# USB-RS232_A2.net
KiCad netlist of a schematic drawn in Altium Designer
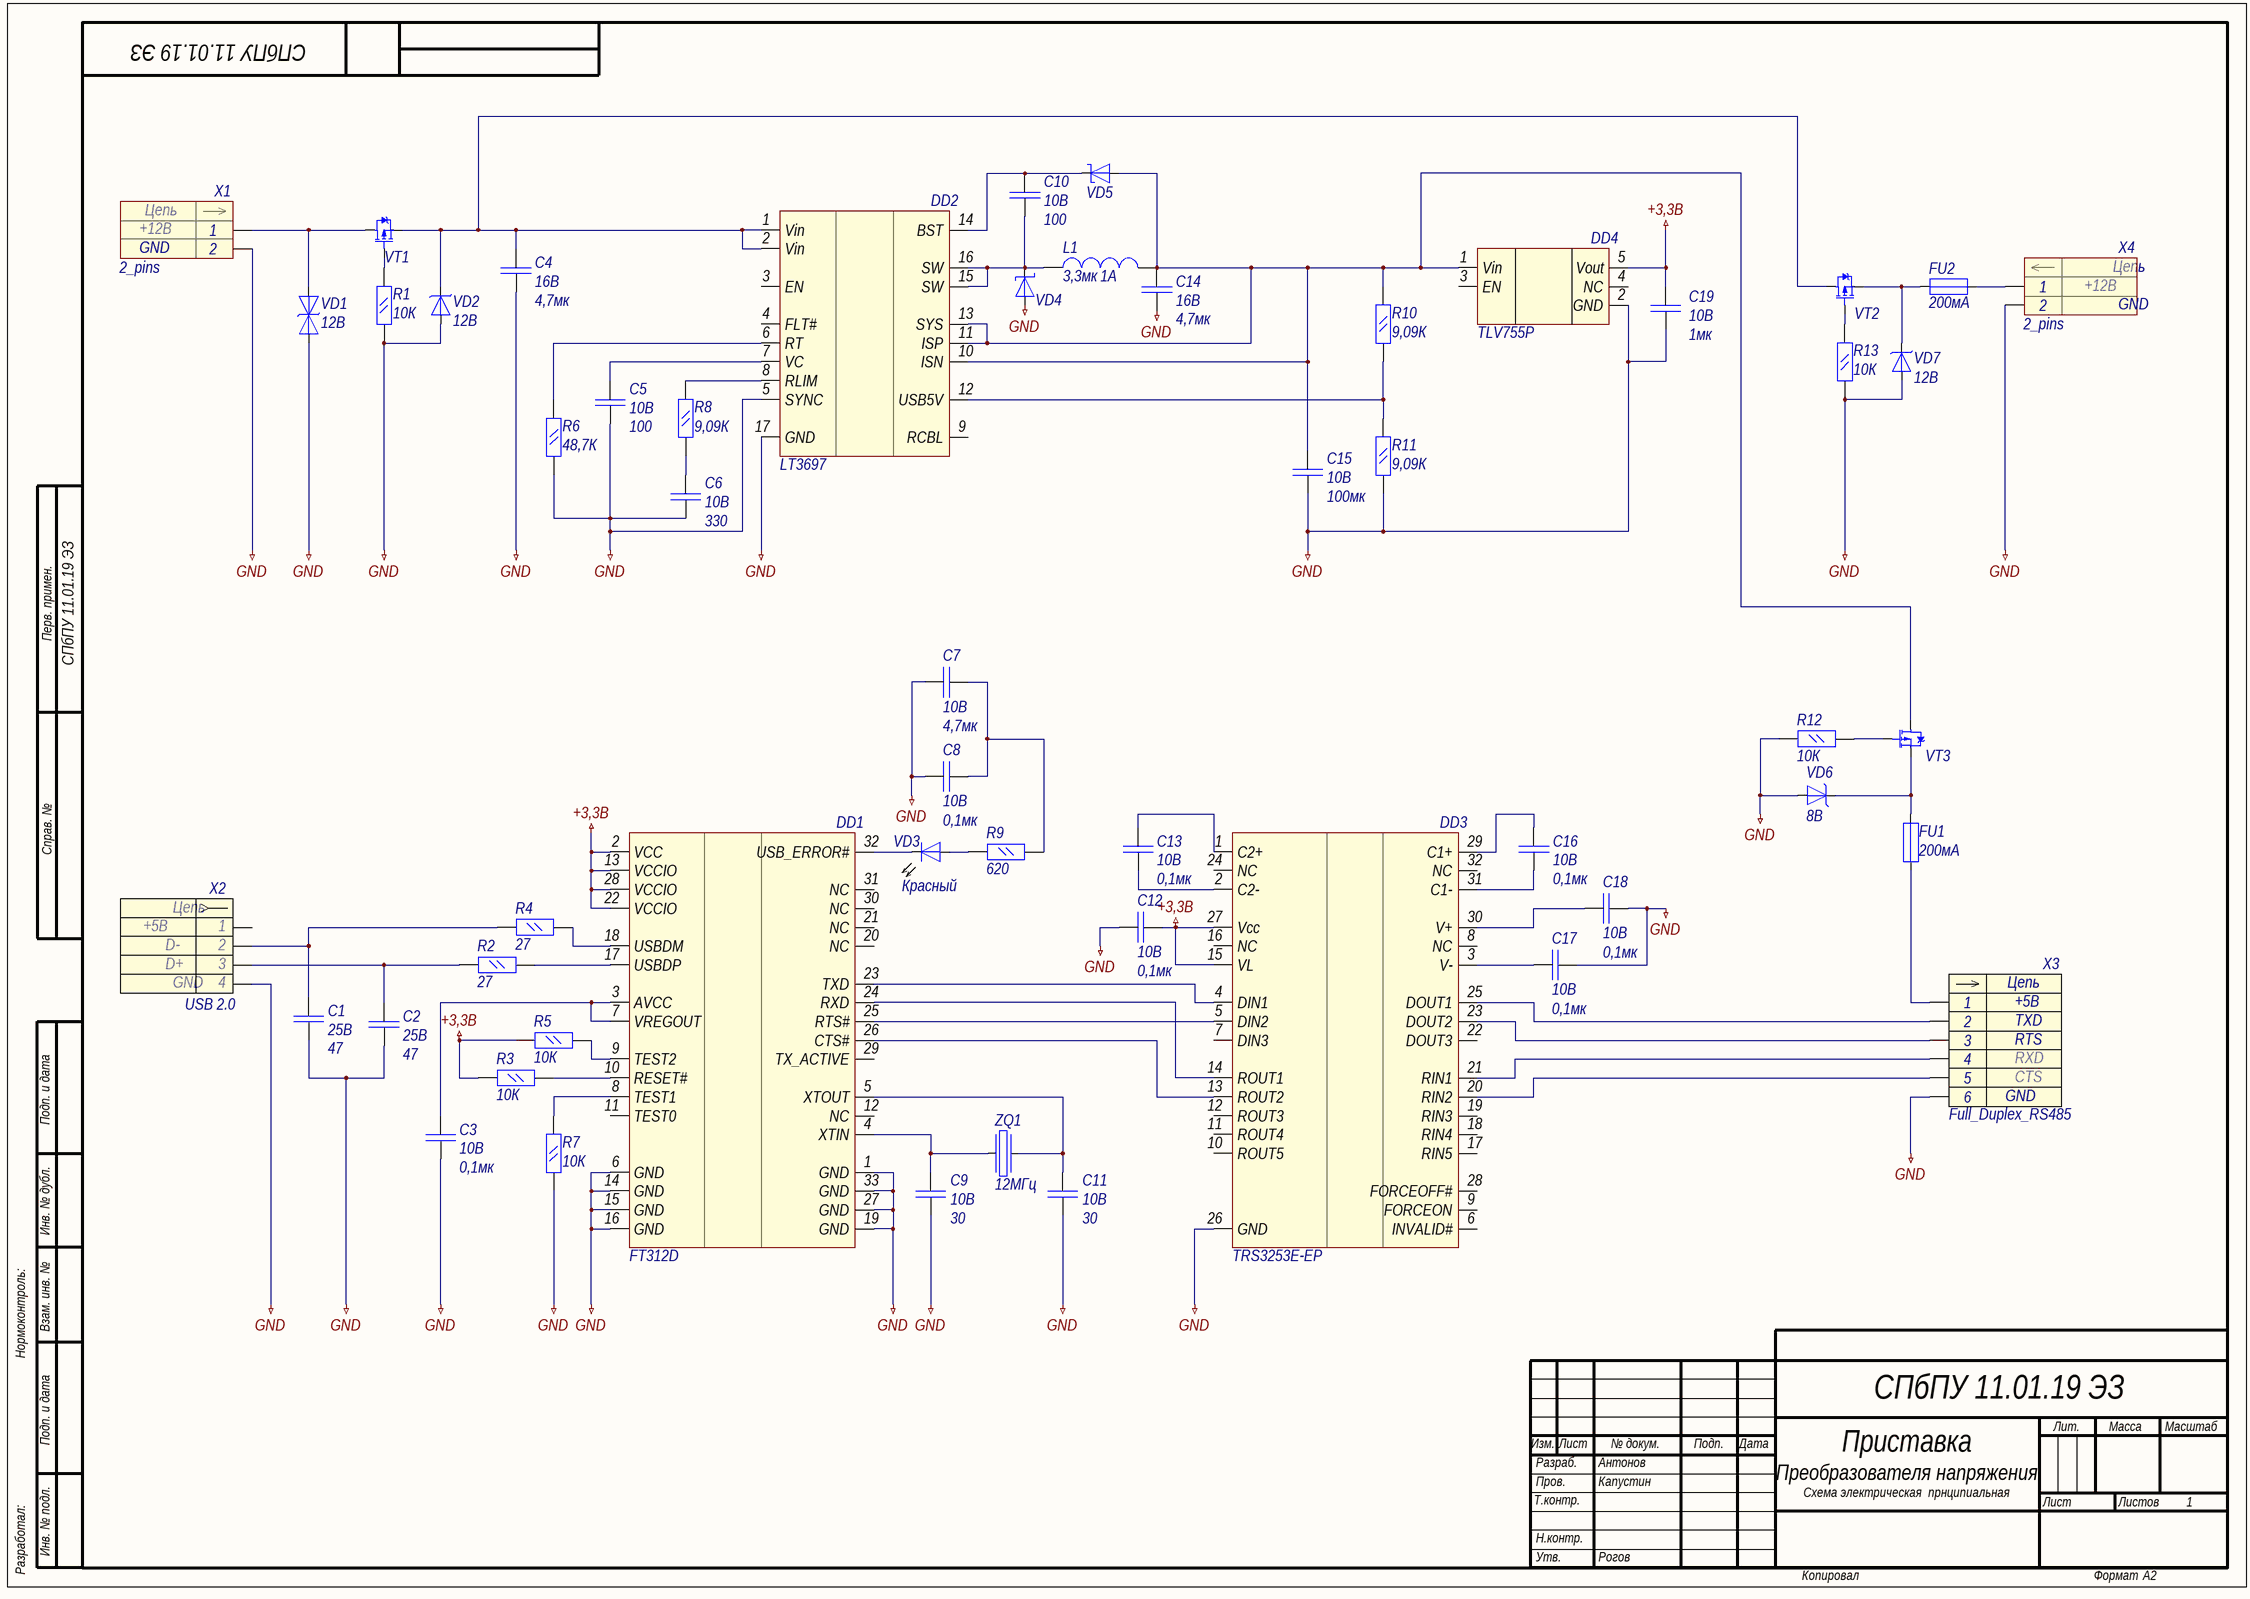
[diagram p0: USB-RS232_A2.SchDoc]

(export (version "E")
  (design (tool "Eeschema 10.0.6"))
  (components
    (comp (ref "C1")
      (value "Capacitor")
      (footprint "CH0201C")
      (fields (field (name "VOLTAGE") "25В") (field (name "CAPACITANCE") "47"))
      (libsource (lib "GOST_Capacitors") (part "Capacitor"))
    )
    (comp (ref "C2")
      (value "Capacitor")
      (footprint "CH0201C")
      (fields (field (name "VOLTAGE") "25В") (field (name "CAPACITANCE") "47"))
      (libsource (lib "GOST_Capacitors") (part "Capacitor"))
    )
    (comp (ref "C3")
      (value "Capacitor")
      (footprint "CH0402C")
      (fields (field (name "VOLTAGE") "10В") (field (name "CAPACITANCE") "0,1мк"))
      (libsource (lib "GOST_Capacitors") (part "Capacitor"))
    )
    (comp (ref "C4")
      (value "Capacitor")
      (footprint "CH0603C")
      (fields (field (name "VOLTAGE") "16В") (field (name "CAPACITANCE") "4,7мк"))
      (libsource (lib "GOST_Capacitors") (part "Capacitor"))
    )
    (comp (ref "C5")
      (value "Capacitor")
      (footprint "CH0201C")
      (fields (field (name "VOLTAGE") "10В") (field (name "CAPACITANCE") "100"))
      (libsource (lib "GOST_Capacitors") (part "Capacitor"))
    )
    (comp (ref "C6")
      (value "Capacitor")
      (footprint "CH0402C")
      (fields (field (name "VOLTAGE") "10В") (field (name "CAPACITANCE") "330"))
      (libsource (lib "GOST_Capacitors") (part "Capacitor"))
    )
    (comp (ref "C7")
      (value "Capacitor")
      (footprint "CH0402C")
      (fields (field (name "VOLTAGE") "10В") (field (name "CAPACITANCE") "4,7мк"))
      (libsource (lib "GOST_Capacitors") (part "Capacitor"))
    )
    (comp (ref "C8")
      (value "Capacitor")
      (footprint "CH0402C")
      (fields (field (name "VOLTAGE") "10В") (field (name "CAPACITANCE") "0,1мк"))
      (libsource (lib "GOST_Capacitors") (part "Capacitor"))
    )
    (comp (ref "C9")
      (value "Capacitor")
      (footprint "CH0201C")
      (fields (field (name "VOLTAGE") "10В") (field (name "CAPACITANCE") "30"))
      (libsource (lib "GOST_Capacitors") (part "Capacitor"))
    )
    (comp (ref "C10")
      (value "Capacitor")
      (footprint "CH0201C")
      (fields (field (name "VOLTAGE") "10В") (field (name "CAPACITANCE") "100"))
      (libsource (lib "GOST_Capacitors") (part "Capacitor"))
    )
    (comp (ref "C11")
      (value "Capacitor")
      (footprint "CH0201C")
      (fields (field (name "VOLTAGE") "10В") (field (name "CAPACITANCE") "30"))
      (libsource (lib "GOST_Capacitors") (part "Capacitor"))
    )
    (comp (ref "C12")
      (value "Capacitor")
      (footprint "CH0402C")
      (fields (field (name "VOLTAGE") "10В") (field (name "CAPACITANCE") "0,1мк"))
      (libsource (lib "GOST_Capacitors") (part "Capacitor"))
    )
    (comp (ref "C13")
      (value "Capacitor")
      (footprint "CH0402C")
      (fields (field (name "VOLTAGE") "10В") (field (name "CAPACITANCE") "0,1мк"))
      (libsource (lib "GOST_Capacitors") (part "Capacitor"))
    )
    (comp (ref "C14")
      (value "Capacitor")
      (footprint "CH0603C")
      (fields (field (name "VOLTAGE") "16В") (field (name "CAPACITANCE") "4,7мк"))
      (libsource (lib "GOST_Capacitors") (part "Capacitor"))
    )
    (comp (ref "C15")
      (value "Capacitor")
      (footprint "CH1206C")
      (fields (field (name "VOLTAGE") "10В") (field (name "CAPACITANCE") "100мк"))
      (libsource (lib "GOST_Capacitors") (part "Capacitor"))
    )
    (comp (ref "C16")
      (value "Capacitor")
      (footprint "CH0402C")
      (fields (field (name "VOLTAGE") "10В") (field (name "CAPACITANCE") "0,1мк"))
      (libsource (lib "GOST_Capacitors") (part "Capacitor"))
    )
    (comp (ref "C17")
      (value "Capacitor")
      (footprint "CH0402C")
      (fields (field (name "VOLTAGE") "10В") (field (name "CAPACITANCE") "0,1мк"))
      (libsource (lib "GOST_Capacitors") (part "Capacitor"))
    )
    (comp (ref "C18")
      (value "Capacitor")
      (footprint "CH0402C")
      (fields (field (name "VOLTAGE") "10В") (field (name "CAPACITANCE") "0,1мк"))
      (libsource (lib "GOST_Capacitors") (part "Capacitor"))
    )
    (comp (ref "C19")
      (value "Capacitor")
      (footprint "CH0201C")
      (fields (field (name "VOLTAGE") "10В") (field (name "CAPACITANCE") "1мк"))
      (libsource (lib "GOST_Capacitors") (part "Capacitor"))
    )
    (comp (ref "DD1")
      (value "FT312D")
      (footprint "FT312D")
      (description "Ivan")
      (libsource (lib "GOST_lib_devices") (part "FT312D"))
    )
    (comp (ref "DD2")
      (value "LT3697")
      (footprint "LT3697")
      (description "6~18 to 5")
      (libsource (lib "GOST_lib_devices") (part "LT3697"))
    )
    (comp (ref "DD3")
      (value "TRS3253E-EP")
      (footprint "TRS3253E-EP")
      (description "UART - RS232")
      (libsource (lib "GOST_lib_devices") (part "TRS3253E-EP"))
    )
    (comp (ref "DD4")
      (value "TLV755P")
      (footprint "SOT23-5")
      (libsource (lib "GOST_lib_devices") (part "LDO +3.3V"))
    )
    (comp (ref "FU1")
      (value "200мА")
      (footprint "CH0402R")
      (fields (field (name "Comment") "Fuse"))
      (libsource (lib "GOST_Miscelanuious") (part "Fuse"))
    )
    (comp (ref "FU2")
      (value "200мА")
      (footprint "CH0402R")
      (fields (field (name "Comment") "Fuse"))
      (libsource (lib "") (part "Fuse_1"))
    )
    (comp (ref "L1")
      (value "*")
      (footprint "CH0805L")
      (fields (field (name "MAX CURRENT") "1А") (field (name "INDUCTANCE") "3,3мк"))
      (libsource (lib "GOST_Inductors") (part "Inductor"))
    )
    (comp (ref "R1")
      (value "Res_0.125")
      (footprint "CH0402R")
      (fields (field (name "IMPEDANCE") "10К"))
      (libsource (lib "GOST_Resistors") (part "Res_0.125"))
    )
    (comp (ref "R2")
      (value "Res_0.125")
      (footprint "CH0402R")
      (fields (field (name "IMPEDANCE") "27"))
      (libsource (lib "GOST_Resistors") (part "Res_0.125"))
    )
    (comp (ref "R3")
      (value "Res_0.125")
      (footprint "CH0402R")
      (fields (field (name "IMPEDANCE") "10К"))
      (libsource (lib "GOST_Resistors") (part "Res_0.125"))
    )
    (comp (ref "R4")
      (value "Res_0.125")
      (footprint "CH0402R")
      (fields (field (name "IMPEDANCE") "27"))
      (libsource (lib "GOST_Resistors") (part "Res_0.125"))
    )
    (comp (ref "R5")
      (value "Res_0.125")
      (footprint "CH0402R")
      (fields (field (name "IMPEDANCE") "10К"))
      (libsource (lib "GOST_Resistors") (part "Res_0.125"))
    )
    (comp (ref "R6")
      (value "Res_0.125")
      (footprint "CH0805R")
      (fields (field (name "IMPEDANCE") "48,7К"))
      (libsource (lib "GOST_Resistors") (part "Res_0.125"))
    )
    (comp (ref "R7")
      (value "Res_0.125")
      (footprint "CH0402R")
      (fields (field (name "IMPEDANCE") "10К"))
      (libsource (lib "GOST_Resistors") (part "Res_0.125"))
    )
    (comp (ref "R8")
      (value "Res_0.125")
      (footprint "CH0805R")
      (fields (field (name "IMPEDANCE") "9,09К"))
      (libsource (lib "GOST_Resistors") (part "Res_0.125"))
    )
    (comp (ref "R9")
      (value "Res_0.125")
      (footprint "CH0402R")
      (fields (field (name "IMPEDANCE") "620"))
      (libsource (lib "GOST_Resistors") (part "Res_0.125"))
    )
    (comp (ref "R10")
      (value "Res_0.125")
      (footprint "CH0805R")
      (fields (field (name "IMPEDANCE") "9,09К"))
      (libsource (lib "GOST_Resistors") (part "Res_0.125"))
    )
    (comp (ref "R11")
      (value "Res_0.125")
      (footprint "CH0805R")
      (fields (field (name "IMPEDANCE") "9,09К"))
      (libsource (lib "GOST_Resistors") (part "Res_0.125"))
    )
    (comp (ref "R12")
      (value "Res_0.125")
      (footprint "CH0402R")
      (fields (field (name "IMPEDANCE") "10К"))
      (libsource (lib "GOST_Resistors") (part "Res_0.125"))
    )
    (comp (ref "R13")
      (value "Res_0.125")
      (footprint "CH0402R")
      (fields (field (name "IMPEDANCE") "10К"))
      (libsource (lib "GOST_Resistors") (part "Res_0.125"))
    )
    (comp (ref "VD1")
      (value "TVS-diod_simmetrical")
      (footprint "CH0201L")
      (fields (field (name "MANUFACTURER") "Littelfuse") (field (name "CLAMPING VOLTAGE") "12В"))
      (libsource (lib "GOST_Diodes") (part "TVS-diod_simmetrical"))
    )
    (comp (ref "VD2")
      (value "TVS-diod_directed")
      (footprint "DO214AA")
      (fields (field (name "MANUFACTURER") "Bourns") (field (name "CLAMPING_VOLTAGE") "12В"))
      (libsource (lib "GOST_Diodes") (part "TVS-diod_directed"))
    )
    (comp (ref "VD3")
      (value "Light_diod")
      (footprint "CH0201L")
      (fields (field (name "COLOR") "Красный"))
      (libsource (lib "GOST_Diodes") (part "Light_diod"))
    )
    (comp (ref "VD4")
      (value "Diod Schottky")
      (footprint "DO214AA")
      (fields (field (name "MANUFACTURER") "Rectron"))
      (libsource (lib "GOST_Diodes") (part "Diod Schottky"))
    )
    (comp (ref "VD5")
      (value "Diod Schottky")
      (footprint "SOT23_132")
      (fields (field (name "MANUFACTURER") "Toshiba"))
      (libsource (lib "GOST_Diodes") (part "Diod Schottky"))
    )
    (comp (ref "VD6")
      (value "TVS-diod_directed")
      (footprint "SOD123W")
      (fields (field (name "MANUFACTURER") "Nexperia") (field (name "CLAMPING_VOLTAGE") "8В"))
      (libsource (lib "GOST_Diodes") (part "TVS-diod_directed"))
    )
    (comp (ref "VD7")
      (value "TVS-diod_directed")
      (footprint "DO214AA")
      (fields (field (name "MANUFACTURER") "Bourns") (field (name "CLAMPING_VOLTAGE") "12В"))
      (libsource (lib "GOST_Diodes") (part "TVS-diod_directed"))
    )
    (comp (ref "VT1")
      (value "*")
      (footprint "SOT23_132")
      (libsource (lib "GOST_Transistors") (part "P-Channel"))
    )
    (comp (ref "VT2")
      (value "*")
      (footprint "SOT23_132")
      (libsource (lib "GOST_Transistors") (part "P-Channel"))
    )
    (comp (ref "VT3")
      (value "*")
      (footprint "SOT23_132")
      (libsource (lib "GOST_Transistors") (part "P-Channel"))
    )
    (comp (ref "X1")
      (value "2_pins")
      (footprint "CON: 163-179PH-EX")
      (fields (field (name "VCC") "+12В"))
      (libsource (lib "GOST_lib_connectors") (part "2_pins"))
    )
    (comp (ref "X2")
      (value "USB 2.0")
      (footprint "Integrated_Library:USB")
      (description "USB")
      (fields (field (name "MANUFACTURER") "TE Connectivity") (field (name "VCC") "+5В"))
      (libsource (lib "Connectors") (part "USB-A"))
    )
    (comp (ref "X3")
      (value "Full_Duplex_RS485")
      (footprint "CON: PBS-6")
      (fields
        (field (name "Z") "RXD")
        (field (name "Y") "CTS")
        (field (name "VCC") "+5В")
        (field (name "A") "TXD")
        (field (name "B") "RTS")
      )
      (libsource (lib "GOST_lib_connectors") (part "Full_Duplex_RS485"))
    )
    (comp (ref "X4")
      (value "2_pins")
      (footprint "CON: PBS-2")
      (fields (field (name "VCC") "+12В"))
      (libsource (lib "") (part "2_pins_1"))
    )
    (comp (ref "ZQ1")
      (value "12МГц")
      (footprint "OSC: 5032")
      (fields (field (name "Comment") "Oscillator"))
      (libsource (lib "GOST_Miscelanuious") (part "Oscillator"))
    )
  )
  (nets
    (net (code "1") (name "+3,3В") (class "Default")
      (node (ref "C12") (pin "2") (pinfunction "C1-_2") (pintype "power_in"))
      (node (ref "C19") (pin "1") (pinfunction "C1+_1") (pintype "power_in"))
      (node (ref "DD1") (pin "13") (pinfunction "VCCIO_13") (pintype "power_in"))
      (node (ref "DD1") (pin "2") (pinfunction "VCC_2") (pintype "power_in"))
      (node (ref "DD1") (pin "22") (pinfunction "VCCIO_22") (pintype "power_in"))
      (node (ref "DD1") (pin "28") (pinfunction "VCCIO_28") (pintype "power_in"))
      (node (ref "DD3") (pin "15") (pinfunction "VL_15") (pintype "power_in"))
      (node (ref "DD3") (pin "27") (pinfunction "Vcc_27") (pintype "power_in"))
      (node (ref "DD4") (pin "5") (pinfunction "Vout_5") (pintype "power_in"))
      (node (ref "R3") (pin "2") (pinfunction "C1-_2") (pintype "power_in"))
      (node (ref "R5") (pin "2") (pinfunction "C1-_2") (pintype "power_in"))
    )
    (net (code "2") (name "GND") (class "Default")
      (node (ref "C1") (pin "2") (pinfunction "C1-_2") (pintype "power_in"))
      (node (ref "C11") (pin "2") (pinfunction "C1-_2") (pintype "power_in"))
      (node (ref "C12") (pin "1") (pinfunction "C1+_1") (pintype "power_in"))
      (node (ref "C14") (pin "2") (pinfunction "C1-_2") (pintype "power_in"))
      (node (ref "C15") (pin "2") (pinfunction "C1-_2") (pintype "power_in"))
      (node (ref "C17") (pin "2") (pinfunction "C1-_2") (pintype "power_in"))
      (node (ref "C18") (pin "2") (pinfunction "C1-_2") (pintype "power_in"))
      (node (ref "C19") (pin "2") (pinfunction "C1-_2") (pintype "power_in"))
      (node (ref "C2") (pin "2") (pinfunction "C1-_2") (pintype "power_in"))
      (node (ref "C3") (pin "2") (pinfunction "C1-_2") (pintype "power_in"))
      (node (ref "C4") (pin "2") (pinfunction "C1-_2") (pintype "power_in"))
      (node (ref "C5") (pin "2") (pinfunction "C1-_2") (pintype "power_in"))
      (node (ref "C6") (pin "2") (pinfunction "C1-_2") (pintype "power_in"))
      (node (ref "C7") (pin "1") (pinfunction "C1+_1") (pintype "power_in"))
      (node (ref "C8") (pin "1") (pinfunction "C1+_1") (pintype "power_in"))
      (node (ref "C9") (pin "2") (pinfunction "C1-_2") (pintype "power_in"))
      (node (ref "DD1") (pin "1") (pinfunction "GND_1") (pintype "power_in"))
      (node (ref "DD1") (pin "14") (pinfunction "GND_14") (pintype "power_in"))
      (node (ref "DD1") (pin "15") (pinfunction "GND_15") (pintype "power_in"))
      (node (ref "DD1") (pin "16") (pinfunction "GND_16") (pintype "power_in"))
      (node (ref "DD1") (pin "19") (pinfunction "GND_19") (pintype "power_in"))
      (node (ref "DD1") (pin "27") (pinfunction "GND_27") (pintype "power_in"))
      (node (ref "DD1") (pin "33") (pinfunction "GND_33") (pintype "power_in"))
      (node (ref "DD1") (pin "6") (pinfunction "GND_6") (pintype "power_in"))
      (node (ref "DD2") (pin "17") (pinfunction "GND_17") (pintype "power_in"))
      (node (ref "DD2") (pin "5") (pinfunction "SYNC_5") (pintype "power_in"))
      (node (ref "DD3") (pin "26") (pinfunction "GND_26") (pintype "power_in"))
      (node (ref "DD4") (pin "2") (pinfunction "GND_2") (pintype "power_in"))
      (node (ref "R1") (pin "1") (pinfunction "C1-_1") (pintype "power_in"))
      (node (ref "R11") (pin "2") (pinfunction "C1-_2") (pintype "power_in"))
      (node (ref "R12") (pin "2") (pinfunction "C1-_2") (pintype "power_in"))
      (node (ref "R13") (pin "1") (pinfunction "C1-_1") (pintype "power_in"))
      (node (ref "R6") (pin "2") (pinfunction "C1-_2") (pintype "power_in"))
      (node (ref "R7") (pin "1") (pinfunction "C1-_1") (pintype "power_in"))
      (node (ref "VD1") (pin "1") (pinfunction "A_1") (pintype "passive"))
      (node (ref "VD2") (pin "1") (pinfunction "A_1") (pintype "passive"))
      (node (ref "VD4") (pin "1") (pinfunction "1_1") (pintype "passive"))
      (node (ref "VD6") (pin "1") (pinfunction "A_1") (pintype "passive"))
      (node (ref "VD7") (pin "1") (pinfunction "A_1") (pintype "passive"))
      (node (ref "X1") (pin "2") (pinfunction "2_2") (pintype "passive"))
      (node (ref "X2") (pin "4") (pinfunction "4_4") (pintype "passive"))
      (node (ref "X3") (pin "6") (pinfunction "6_6") (pintype "passive"))
      (node (ref "X4") (pin "2") (pinfunction "2_2") (pintype "passive"))
    )
    (net (code "3") (name "Net-(C1-C1+)") (class "Default")
      (node (ref "C1") (pin "1") (pinfunction "C1+_1") (pintype "power_in"))
      (node (ref "R4") (pin "2") (pinfunction "C1-_2") (pintype "power_in"))
      (node (ref "X2") (pin "2") (pinfunction "2_2") (pintype "passive"))
    )
    (net (code "4") (name "Net-(C2-C1+)") (class "Default")
      (node (ref "C2") (pin "1") (pinfunction "C1+_1") (pintype "power_in"))
      (node (ref "R2") (pin "2") (pinfunction "C1-_2") (pintype "power_in"))
      (node (ref "X2") (pin "3") (pinfunction "3_3") (pintype "passive"))
    )
    (net (code "5") (name "Net-(C3-C1+)") (class "Default")
      (node (ref "C3") (pin "1") (pinfunction "C1+_1") (pintype "power_in"))
      (node (ref "DD1") (pin "3") (pinfunction "AVCC_3") (pintype "power_in"))
      (node (ref "DD1") (pin "7") (pinfunction "VREGOUT_7") (pintype "power_in"))
    )
    (net (code "6") (name "Net-(C4-C1+)") (class "Default")
      (node (ref "C4") (pin "1") (pinfunction "C1+_1") (pintype "power_in"))
      (node (ref "DD2") (pin "1") (pinfunction "Vin_1") (pintype "power_in"))
      (node (ref "DD2") (pin "2") (pinfunction "Vin_2") (pintype "power_in"))
      (node (ref "VD2") (pin "2") (pinfunction "C_2") (pintype "passive"))
      (node (ref "VT1") (pin "3") (pinfunction "S_3") (pintype "passive"))
      (node (ref "VT2") (pin "2") (pinfunction "D_2") (pintype "passive"))
    )
    (net (code "7") (name "Net-(C5-C1+)") (class "Default")
      (node (ref "C5") (pin "1") (pinfunction "C1+_1") (pintype "power_in"))
      (node (ref "DD2") (pin "7") (pinfunction "VC_7") (pintype "power_in"))
    )
    (net (code "8") (name "Net-(C6-C1+)") (class "Default")
      (node (ref "C6") (pin "1") (pinfunction "C1+_1") (pintype "power_in"))
      (node (ref "R8") (pin "2") (pinfunction "C1-_2") (pintype "power_in"))
    )
    (net (code "9") (name "Net-(C7-C1-)") (class "Default")
      (node (ref "C7") (pin "2") (pinfunction "C1-_2") (pintype "power_in"))
      (node (ref "C8") (pin "2") (pinfunction "C1-_2") (pintype "power_in"))
      (node (ref "R9") (pin "1") (pinfunction "C1-_1") (pintype "power_in"))
    )
    (net (code "10") (name "Net-(C9-C1+)") (class "Default")
      (node (ref "C9") (pin "1") (pinfunction "C1+_1") (pintype "power_in"))
      (node (ref "DD1") (pin "4") (pinfunction "XTIN_4") (pintype "power_in"))
      (node (ref "ZQ1") (pin "1") (pinfunction "1_1") (pintype "passive"))
    )
    (net (code "11") (name "Net-(C10-C1+)") (class "Default")
      (node (ref "C10") (pin "1") (pinfunction "C1+_1") (pintype "power_in"))
      (node (ref "DD2") (pin "14") (pinfunction "BST_14") (pintype "power_in"))
      (node (ref "VD5") (pin "2") (pinfunction "2_2") (pintype "passive"))
    )
    (net (code "12") (name "Net-(C10-C1-)") (class "Default")
      (node (ref "C10") (pin "2") (pinfunction "C1-_2") (pintype "power_in"))
      (node (ref "DD2") (pin "15") (pinfunction "SW_15") (pintype "power_in"))
      (node (ref "DD2") (pin "16") (pinfunction "SW_16") (pintype "power_in"))
      (node (ref "L1") (pin "1") (pinfunction "C1-_1") (pintype "power_in"))
      (node (ref "VD4") (pin "2") (pinfunction "2_2") (pintype "passive"))
    )
    (net (code "13") (name "Net-(C11-C1+)") (class "Default")
      (node (ref "C11") (pin "1") (pinfunction "C1+_1") (pintype "power_in"))
      (node (ref "DD1") (pin "5") (pinfunction "XTOUT_5") (pintype "power_in"))
      (node (ref "ZQ1") (pin "3") (pinfunction "3_3") (pintype "passive"))
    )
    (net (code "14") (name "Net-(C13-C1+)") (class "Default")
      (node (ref "C13") (pin "1") (pinfunction "C1+_1") (pintype "power_in"))
      (node (ref "DD3") (pin "1") (pinfunction "C2+_1") (pintype "power_in"))
    )
    (net (code "15") (name "Net-(C13-C1-)") (class "Default")
      (node (ref "C13") (pin "2") (pinfunction "C1-_2") (pintype "power_in"))
      (node (ref "DD3") (pin "2") (pinfunction "C2-_2") (pintype "power_in"))
    )
    (net (code "16") (name "Net-(C14-C1+)") (class "Default")
      (node (ref "C14") (pin "1") (pinfunction "C1+_1") (pintype "power_in"))
      (node (ref "C15") (pin "1") (pinfunction "C1+_1") (pintype "power_in"))
      (node (ref "DD2") (pin "10") (pinfunction "ISN_10") (pintype "power_in"))
      (node (ref "DD2") (pin "11") (pinfunction "ISP_11") (pintype "power_in"))
      (node (ref "DD2") (pin "13") (pinfunction "SYS_13") (pintype "power_in"))
      (node (ref "DD4") (pin "1") (pinfunction "Vin_1") (pintype "power_in"))
      (node (ref "L1") (pin "2") (pinfunction "14_2") (pintype "power_in"))
      (node (ref "R10") (pin "1") (pinfunction "C1-_1") (pintype "power_in"))
      (node (ref "VD5") (pin "1") (pinfunction "1_1") (pintype "passive"))
      (node (ref "VT3") (pin "2") (pinfunction "D_2") (pintype "passive"))
    )
    (net (code "17") (name "Net-(C16-C1+)") (class "Default")
      (node (ref "C16") (pin "1") (pinfunction "C1+_1") (pintype "power_in"))
      (node (ref "DD3") (pin "29") (pinfunction "C1+_29") (pintype "power_in"))
    )
    (net (code "18") (name "Net-(C16-C1-)") (class "Default")
      (node (ref "C16") (pin "2") (pinfunction "C1-_2") (pintype "power_in"))
      (node (ref "DD3") (pin "31") (pinfunction "C1-_31") (pintype "power_in"))
    )
    (net (code "19") (name "Net-(C17-C1+)") (class "Default")
      (node (ref "C17") (pin "1") (pinfunction "C1+_1") (pintype "power_in"))
      (node (ref "DD3") (pin "3") (pinfunction "V-_3") (pintype "power_in"))
    )
    (net (code "20") (name "Net-(C18-C1+)") (class "Default")
      (node (ref "C18") (pin "1") (pinfunction "C1+_1") (pintype "power_in"))
      (node (ref "DD3") (pin "30") (pinfunction "V+_30") (pintype "power_in"))
    )
    (net (code "21") (name "Net-(DD1-CTS#)") (class "Default")
      (node (ref "DD1") (pin "26") (pinfunction "CTS#_26") (pintype "power_in"))
      (node (ref "DD3") (pin "13") (pinfunction "ROUT2_13") (pintype "power_in"))
    )
    (net (code "22") (name "Net-(DD1-RESET#)") (class "Default")
      (node (ref "DD1") (pin "10") (pinfunction "RESET#_10") (pintype "power_in"))
      (node (ref "R3") (pin "1") (pinfunction "C1-_1") (pintype "power_in"))
    )
    (net (code "23") (name "Net-(DD1-RTS#)") (class "Default")
      (node (ref "DD1") (pin "25") (pinfunction "RTS#_25") (pintype "power_in"))
      (node (ref "DD3") (pin "5") (pinfunction "DIN2_5") (pintype "power_in"))
    )
    (net (code "24") (name "Net-(DD1-RXD)") (class "Default")
      (node (ref "DD1") (pin "24") (pinfunction "RXD_24") (pintype "power_in"))
      (node (ref "DD3") (pin "14") (pinfunction "ROUT1_14") (pintype "power_in"))
    )
    (net (code "25") (name "Net-(DD1-TEST1)") (class "Default")
      (node (ref "DD1") (pin "8") (pinfunction "TEST1_8") (pintype "power_in"))
      (node (ref "R7") (pin "2") (pinfunction "C1-_2") (pintype "power_in"))
    )
    (net (code "26") (name "Net-(DD1-TEST2)") (class "Default")
      (node (ref "DD1") (pin "9") (pinfunction "TEST2_9") (pintype "power_in"))
      (node (ref "R5") (pin "1") (pinfunction "C1-_1") (pintype "power_in"))
    )
    (net (code "27") (name "Net-(DD1-TXD)") (class "Default")
      (node (ref "DD1") (pin "23") (pinfunction "TXD_23") (pintype "power_in"))
      (node (ref "DD3") (pin "4") (pinfunction "DIN1_4") (pintype "power_in"))
    )
    (net (code "28") (name "Net-(DD1-USBDM)") (class "Default")
      (node (ref "DD1") (pin "18") (pinfunction "USBDM_18") (pintype "power_in"))
      (node (ref "R4") (pin "1") (pinfunction "C1-_1") (pintype "power_in"))
    )
    (net (code "29") (name "Net-(DD1-USBDP)") (class "Default")
      (node (ref "DD1") (pin "17") (pinfunction "USBDP_17") (pintype "power_in"))
      (node (ref "R2") (pin "1") (pinfunction "C1-_1") (pintype "power_in"))
    )
    (net (code "30") (name "Net-(DD1-USB_ERROR#)") (class "Default")
      (node (ref "DD1") (pin "32") (pinfunction "USB_ERROR#_32") (pintype "power_in"))
      (node (ref "VD3") (pin "2") (pinfunction "2_2") (pintype "passive"))
    )
    (net (code "31") (name "Net-(DD2-RLIM)") (class "Default")
      (node (ref "DD2") (pin "8") (pinfunction "RLIM_8") (pintype "power_in"))
      (node (ref "R8") (pin "1") (pinfunction "C1-_1") (pintype "power_in"))
    )
    (net (code "32") (name "Net-(DD2-RT)") (class "Default")
      (node (ref "DD2") (pin "6") (pinfunction "RT_6") (pintype "power_in"))
      (node (ref "R6") (pin "1") (pinfunction "C1-_1") (pintype "power_in"))
    )
    (net (code "33") (name "Net-(DD2-USB5V)") (class "Default")
      (node (ref "DD2") (pin "12") (pinfunction "USB5V_12") (pintype "power_in"))
      (node (ref "R10") (pin "2") (pinfunction "C1-_2") (pintype "power_in"))
      (node (ref "R11") (pin "1") (pinfunction "C1-_1") (pintype "power_in"))
    )
    (net (code "34") (name "Net-(DD3-DOUT1)") (class "Default")
      (node (ref "DD3") (pin "25") (pinfunction "DOUT1_25") (pintype "power_in"))
      (node (ref "X3") (pin "2") (pinfunction "2_2") (pintype "passive"))
    )
    (net (code "35") (name "Net-(DD3-DOUT2)") (class "Default")
      (node (ref "DD3") (pin "23") (pinfunction "DOUT2_23") (pintype "power_in"))
      (node (ref "X3") (pin "3") (pinfunction "3_3") (pintype "passive"))
    )
    (net (code "36") (name "Net-(DD3-RIN1)") (class "Default")
      (node (ref "DD3") (pin "21") (pinfunction "RIN1_21") (pintype "power_in"))
      (node (ref "X3") (pin "4") (pinfunction "4_4") (pintype "passive"))
    )
    (net (code "37") (name "Net-(DD3-RIN2)") (class "Default")
      (node (ref "DD3") (pin "20") (pinfunction "RIN2_20") (pintype "power_in"))
      (node (ref "X3") (pin "5") (pinfunction "5_5") (pintype "passive"))
    )
    (net (code "38") (name "Net-(FU1-Pad1)") (class "Default")
      (node (ref "FU1") (pin "1") (pinfunction "1_1") (pintype "passive"))
      (node (ref "X3") (pin "1") (pinfunction "1_1") (pintype "passive"))
    )
    (net (code "39") (name "Net-(FU2-Pad2)") (class "Default")
      (node (ref "FU2") (pin "2") (pinfunction "2_2") (pintype "passive"))
      (node (ref "X4") (pin "1") (pinfunction "1_1") (pintype "passive"))
    )
    (net (code "40") (name "Net-(R9-C1--Pad2)") (class "Default")
      (node (ref "R9") (pin "2") (pinfunction "C1-_2") (pintype "power_in"))
      (node (ref "VD3") (pin "1") (pinfunction "1_1") (pintype "passive"))
    )
    (net (code "41") (name "Net-(VD1-C)") (class "Default")
      (node (ref "VD1") (pin "2") (pinfunction "C_2") (pintype "passive"))
      (node (ref "VT1") (pin "2") (pinfunction "D_2") (pintype "passive"))
      (node (ref "X1") (pin "1") (pinfunction "1_1") (pintype "passive"))
    )
    (net (code "42") (name "Net-(VD6-C)") (class "Default")
      (node (ref "FU1") (pin "2") (pinfunction "2_2") (pintype "passive"))
      (node (ref "VD6") (pin "2") (pinfunction "C_2") (pintype "passive"))
      (node (ref "VT3") (pin "3") (pinfunction "S_3") (pintype "passive"))
    )
    (net (code "43") (name "Net-(VD7-C)") (class "Default")
      (node (ref "FU2") (pin "1") (pinfunction "1_1") (pintype "passive"))
      (node (ref "VD7") (pin "2") (pinfunction "C_2") (pintype "passive"))
      (node (ref "VT2") (pin "3") (pinfunction "S_3") (pintype "passive"))
    )
    (net (code "44") (name "Net-(VT1-G)") (class "Default")
      (node (ref "R1") (pin "2") (pinfunction "C1-_2") (pintype "power_in"))
      (node (ref "VT1") (pin "1") (pinfunction "G_1") (pintype "passive"))
    )
    (net (code "45") (name "Net-(VT2-G)") (class "Default")
      (node (ref "R13") (pin "2") (pinfunction "C1-_2") (pintype "power_in"))
      (node (ref "VT2") (pin "1") (pinfunction "G_1") (pintype "passive"))
    )
    (net (code "46") (name "Net-(VT3-G)") (class "Default")
      (node (ref "R12") (pin "1") (pinfunction "C1-_1") (pintype "power_in"))
      (node (ref "VT3") (pin "1") (pinfunction "G_1") (pintype "passive"))
    )
    (net (code "47") (name "unconnected-(DD1-NC-Pad12)") (class "Default")
      (node (ref "DD1") (pin "12") (pinfunction "NC_12") (pintype "power_in"))
    )
    (net (code "48") (name "unconnected-(DD1-NC-Pad20)") (class "Default")
      (node (ref "DD1") (pin "20") (pinfunction "NC_20") (pintype "power_in"))
    )
    (net (code "49") (name "unconnected-(DD1-NC-Pad21)") (class "Default")
      (node (ref "DD1") (pin "21") (pinfunction "NC_21") (pintype "power_in"))
    )
    (net (code "50") (name "unconnected-(DD1-NC-Pad30)") (class "Default")
      (node (ref "DD1") (pin "30") (pinfunction "NC_30") (pintype "power_in"))
    )
    (net (code "51") (name "unconnected-(DD1-NC-Pad31)") (class "Default")
      (node (ref "DD1") (pin "31") (pinfunction "NC_31") (pintype "power_in"))
    )
    (net (code "52") (name "unconnected-(DD1-TEST0-Pad11)") (class "Default")
      (node (ref "DD1") (pin "11") (pinfunction "TEST0_11") (pintype "power_in"))
    )
    (net (code "53") (name "unconnected-(DD1-TX_ACTIVE-Pad29)") (class "Default")
      (node (ref "DD1") (pin "29") (pinfunction "TX_ACTIVE_29") (pintype "power_in"))
    )
    (net (code "54") (name "unconnected-(DD2-EN-Pad3)") (class "Default")
      (node (ref "DD2") (pin "3") (pinfunction "EN_3") (pintype "power_in"))
    )
    (net (code "55") (name "unconnected-(DD2-FLT#-Pad4)") (class "Default")
      (node (ref "DD2") (pin "4") (pinfunction "FLT#_4") (pintype "power_in"))
    )
    (net (code "56") (name "unconnected-(DD2-RCBL-Pad9)") (class "Default")
      (node (ref "DD2") (pin "9") (pinfunction "RCBL_9") (pintype "power_in"))
    )
    (net (code "57") (name "unconnected-(DD3-DIN3-Pad7)") (class "Default")
      (node (ref "DD3") (pin "7") (pinfunction "DIN3_7") (pintype "power_in"))
    )
    (net (code "58") (name "unconnected-(DD3-DOUT3-Pad22)") (class "Default")
      (node (ref "DD3") (pin "22") (pinfunction "DOUT3_22") (pintype "power_in"))
    )
    (net (code "59") (name "unconnected-(DD3-FORCEOFF#-Pad28)") (class "Default")
      (node (ref "DD3") (pin "28") (pinfunction "FORCEOFF#_28") (pintype "power_in"))
    )
    (net (code "60") (name "unconnected-(DD3-FORCEON-Pad9)") (class "Default")
      (node (ref "DD3") (pin "9") (pinfunction "FORCEON_9") (pintype "power_in"))
    )
    (net (code "61") (name "unconnected-(DD3-INVALID#-Pad6)") (class "Default")
      (node (ref "DD3") (pin "6") (pinfunction "INVALID#_6") (pintype "power_in"))
    )
    (net (code "62") (name "unconnected-(DD3-NC-Pad8)") (class "Default")
      (node (ref "DD3") (pin "8") (pinfunction "NC_8") (pintype "power_in"))
    )
    (net (code "63") (name "unconnected-(DD3-NC-Pad16)") (class "Default")
      (node (ref "DD3") (pin "16") (pinfunction "NC_16") (pintype "power_in"))
    )
    (net (code "64") (name "unconnected-(DD3-NC-Pad24)") (class "Default")
      (node (ref "DD3") (pin "24") (pinfunction "NC_24") (pintype "power_in"))
    )
    (net (code "65") (name "unconnected-(DD3-NC-Pad32)") (class "Default")
      (node (ref "DD3") (pin "32") (pinfunction "NC_32") (pintype "power_in"))
    )
    (net (code "66") (name "unconnected-(DD3-RIN3-Pad19)") (class "Default")
      (node (ref "DD3") (pin "19") (pinfunction "RIN3_19") (pintype "power_in"))
    )
    (net (code "67") (name "unconnected-(DD3-RIN4-Pad18)") (class "Default")
      (node (ref "DD3") (pin "18") (pinfunction "RIN4_18") (pintype "power_in"))
    )
    (net (code "68") (name "unconnected-(DD3-RIN5-Pad17)") (class "Default")
      (node (ref "DD3") (pin "17") (pinfunction "RIN5_17") (pintype "power_in"))
    )
    (net (code "69") (name "unconnected-(DD3-ROUT3-Pad12)") (class "Default")
      (node (ref "DD3") (pin "12") (pinfunction "ROUT3_12") (pintype "power_in"))
    )
    (net (code "70") (name "unconnected-(DD3-ROUT4-Pad11)") (class "Default")
      (node (ref "DD3") (pin "11") (pinfunction "ROUT4_11") (pintype "power_in"))
    )
    (net (code "71") (name "unconnected-(DD3-ROUT5-Pad10)") (class "Default")
      (node (ref "DD3") (pin "10") (pinfunction "ROUT5_10") (pintype "power_in"))
    )
    (net (code "72") (name "unconnected-(DD4-EN-Pad3)") (class "Default")
      (node (ref "DD4") (pin "3") (pinfunction "EN_3") (pintype "power_in"))
    )
    (net (code "73") (name "unconnected-(DD4-NC-Pad4)") (class "Default")
      (node (ref "DD4") (pin "4") (pinfunction "NC_4") (pintype "power_in"))
    )
    (net (code "74") (name "unconnected-(X2-Pad1)") (class "Default")
      (node (ref "X2") (pin "1") (pintype "passive"))
    )
  )
)
